# IO_Expansion.net
KiCad netlist of a schematic drawn in Altium Designer
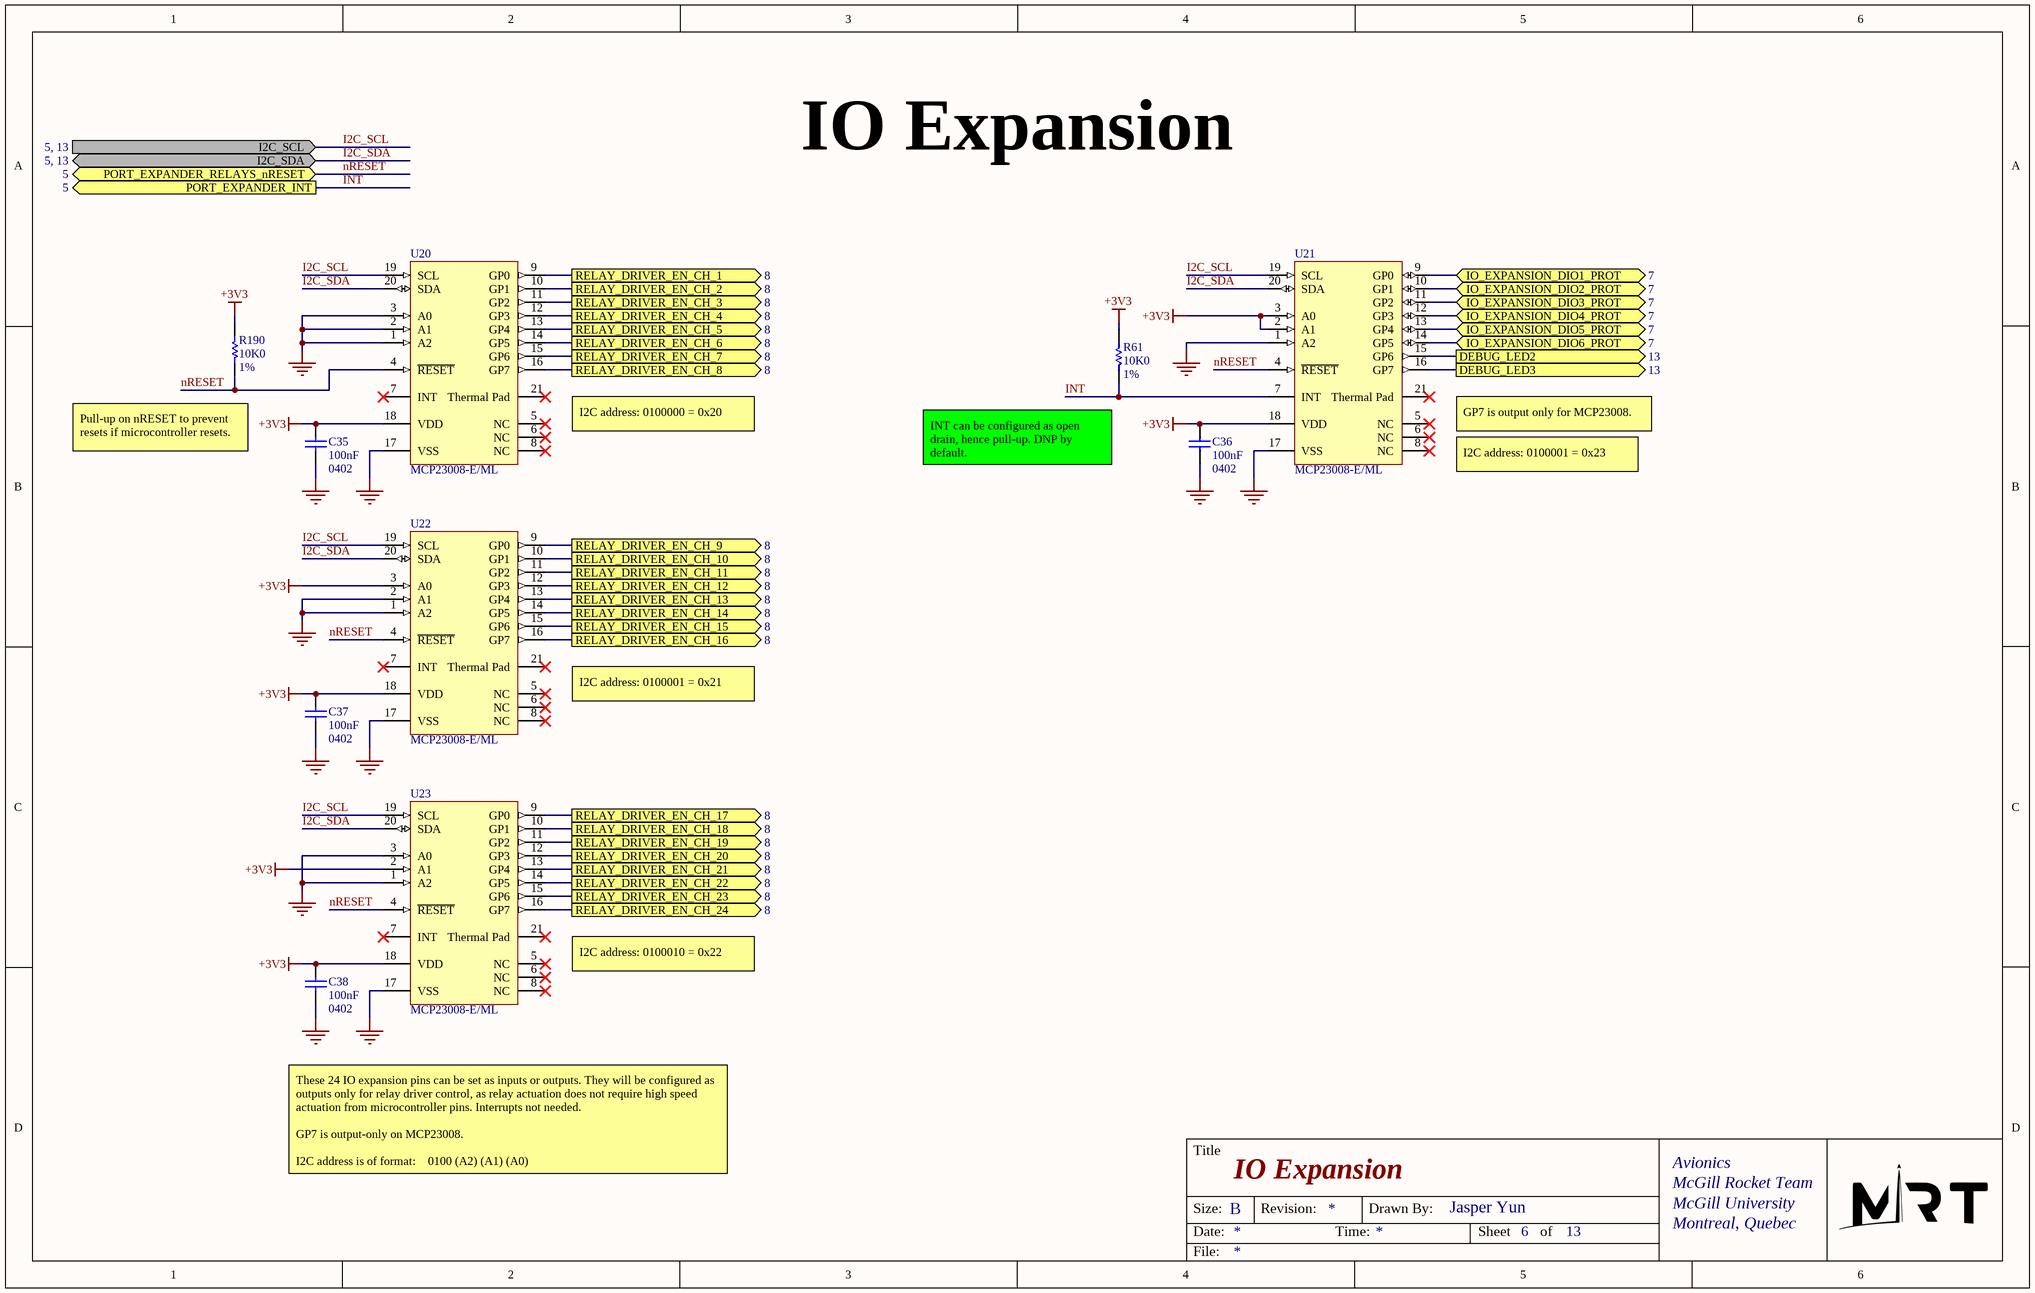
[diagram p0: IO Expansion.SchDoc]

(export (version "E")
  (design (tool "Eeschema 10.0.6"))
  (components
    (comp (ref "C35")
      (value "100nF")
      (footprint "0402 CAP")
      (description "Capacitor")
      (fields (field (name "ALTIUM_VALUE") "0402") (field (name "PUBLISHER") "Altium Limited"))
      (libsource (lib "Miscellaneous Devices") (part "Cap"))
    )
    (comp (ref "C36")
      (value "100nF")
      (footprint "0402 CAP")
      (description "Capacitor")
      (fields (field (name "ALTIUM_VALUE") "0402") (field (name "PUBLISHER") "Altium Limited"))
      (libsource (lib "Miscellaneous Devices") (part "Cap"))
    )
    (comp (ref "C37")
      (value "100nF")
      (footprint "0402 CAP")
      (description "Capacitor")
      (fields (field (name "ALTIUM_VALUE") "0402") (field (name "PUBLISHER") "Altium Limited"))
      (libsource (lib "Miscellaneous Devices") (part "Cap"))
    )
    (comp (ref "C38")
      (value "100nF")
      (footprint "0402 CAP")
      (description "Capacitor")
      (fields (field (name "ALTIUM_VALUE") "0402") (field (name "PUBLISHER") "Altium Limited"))
      (libsource (lib "Miscellaneous Devices") (part "Cap"))
    )
    (comp (ref "R61")
      (value "10K0")
      (footprint "0402 RES")
      (description "Resistor")
      (fields (field (name "ALTIUM_VALUE") "1%") (field (name "PUBLISHER") "Altium Limited"))
      (libsource (lib "Miscellaneous Devices") (part "Res1"))
    )
    (comp (ref "R190")
      (value "10K0")
      (footprint "0402 RES")
      (description "Resistor")
      (fields (field (name "ALTIUM_VALUE") "1%") (field (name "PUBLISHER") "Altium Limited"))
      (libsource (lib "Miscellaneous Devices") (part "Res1"))
    )
    (comp (ref "U20")
      (value "MCP23008-E/ML")
      (footprint "QFN-ML20_M")
      (description "8-Bit I/O Expander with Serial Interface, 20-Pin QFN, Extended Temperature")
      (libsource (lib "Altium Content Vault") (part "PR-BUSIC-MCP23008-21"))
    )
    (comp (ref "U21")
      (value "MCP23008-E/ML")
      (footprint "QFN-ML20_M")
      (description "8-Bit I/O Expander with Serial Interface, 20-Pin QFN, Extended Temperature")
      (libsource (lib "Altium Content Vault") (part "PR-BUSIC-MCP23008-21"))
    )
    (comp (ref "U22")
      (value "MCP23008-E/ML")
      (footprint "QFN-ML20_M")
      (description "8-Bit I/O Expander with Serial Interface, 20-Pin QFN, Extended Temperature")
      (libsource (lib "Altium Content Vault") (part "PR-BUSIC-MCP23008-21"))
    )
    (comp (ref "U23")
      (value "MCP23008-E/ML")
      (footprint "QFN-ML20_M")
      (description "8-Bit I/O Expander with Serial Interface, 20-Pin QFN, Extended Temperature")
      (libsource (lib "Altium Content Vault") (part "PR-BUSIC-MCP23008-21"))
    )
  )
  (nets
    (net (code "1") (name "+3V3") (class "Default")
      (node (ref "C35") (pin "2") (pinfunction "2_2") (pintype "passive"))
      (node (ref "C36") (pin "2") (pinfunction "2_2") (pintype "passive"))
      (node (ref "C37") (pin "2") (pinfunction "2_2") (pintype "passive"))
      (node (ref "C38") (pin "2") (pinfunction "2_2") (pintype "passive"))
      (node (ref "R190") (pin "1") (pinfunction "1_1") (pintype "passive"))
      (node (ref "R61") (pin "1") (pinfunction "1_1") (pintype "passive"))
      (node (ref "U20") (pin "18") (pinfunction "VDD_18") (pintype "power_in"))
      (node (ref "U21") (pin "18") (pinfunction "VDD_18") (pintype "power_in"))
      (node (ref "U21") (pin "2") (pinfunction "A1_2") (pintype "input"))
      (node (ref "U21") (pin "3") (pinfunction "A0_3") (pintype "input"))
      (node (ref "U22") (pin "18") (pinfunction "VDD_18") (pintype "power_in"))
      (node (ref "U22") (pin "3") (pinfunction "A0_3") (pintype "input"))
      (node (ref "U23") (pin "18") (pinfunction "VDD_18") (pintype "power_in"))
      (node (ref "U23") (pin "2") (pinfunction "A1_2") (pintype "input"))
    )
    (net (code "2") (name "/DEBUG_LED2") (class "Default")
      (node (ref "U21") (pin "15") (pinfunction "GP6_15") (pintype "output"))
    )
    (net (code "3") (name "/DEBUG_LED3") (class "Default")
      (node (ref "U21") (pin "16") (pinfunction "GP7_16") (pintype "output"))
    )
    (net (code "4") (name "/I2C_SCL") (class "Default")
      (node (ref "U20") (pin "19") (pinfunction "SCL_19") (pintype "input"))
      (node (ref "U21") (pin "19") (pinfunction "SCL_19") (pintype "input"))
      (node (ref "U22") (pin "19") (pinfunction "SCL_19") (pintype "input"))
      (node (ref "U23") (pin "19") (pinfunction "SCL_19") (pintype "input"))
    )
    (net (code "5") (name "/I2C_SDA") (class "Default")
      (node (ref "U20") (pin "20") (pinfunction "SDA_20") (pintype "bidirectional"))
      (node (ref "U21") (pin "20") (pinfunction "SDA_20") (pintype "bidirectional"))
      (node (ref "U22") (pin "20") (pinfunction "SDA_20") (pintype "bidirectional"))
      (node (ref "U23") (pin "20") (pinfunction "SDA_20") (pintype "bidirectional"))
    )
    (net (code "6") (name "/INT") (class "Default")
      (node (ref "R61") (pin "2") (pinfunction "2_2") (pintype "passive"))
      (node (ref "U21") (pin "7") (pinfunction "INT_7") (pintype "open_collector"))
    )
    (net (code "7") (name "/IO_EXPANSION_DIO1_PROT") (class "Default")
      (node (ref "U21") (pin "9") (pinfunction "GP0_9") (pintype "output"))
    )
    (net (code "8") (name "/IO_EXPANSION_DIO2_PROT") (class "Default")
      (node (ref "U21") (pin "10") (pinfunction "GP1_10") (pintype "output"))
    )
    (net (code "9") (name "/IO_EXPANSION_DIO3_PROT") (class "Default")
      (node (ref "U21") (pin "11") (pinfunction "GP2_11") (pintype "output"))
    )
    (net (code "10") (name "/IO_EXPANSION_DIO4_PROT") (class "Default")
      (node (ref "U21") (pin "12") (pinfunction "GP3_12") (pintype "output"))
    )
    (net (code "11") (name "/IO_EXPANSION_DIO5_PROT") (class "Default")
      (node (ref "U21") (pin "13") (pinfunction "GP4_13") (pintype "output"))
    )
    (net (code "12") (name "/IO_EXPANSION_DIO6_PROT") (class "Default")
      (node (ref "U21") (pin "14") (pinfunction "GP5_14") (pintype "output"))
    )
    (net (code "13") (name "/RELAY_DRIVER_EN_CH_1") (class "Default")
      (node (ref "U20") (pin "9") (pinfunction "GP0_9") (pintype "output"))
    )
    (net (code "14") (name "/RELAY_DRIVER_EN_CH_2") (class "Default")
      (node (ref "U20") (pin "10") (pinfunction "GP1_10") (pintype "output"))
    )
    (net (code "15") (name "/RELAY_DRIVER_EN_CH_3") (class "Default")
      (node (ref "U20") (pin "11") (pinfunction "GP2_11") (pintype "output"))
    )
    (net (code "16") (name "/RELAY_DRIVER_EN_CH_4") (class "Default")
      (node (ref "U20") (pin "12") (pinfunction "GP3_12") (pintype "output"))
    )
    (net (code "17") (name "/RELAY_DRIVER_EN_CH_5") (class "Default")
      (node (ref "U20") (pin "13") (pinfunction "GP4_13") (pintype "output"))
    )
    (net (code "18") (name "/RELAY_DRIVER_EN_CH_6") (class "Default")
      (node (ref "U20") (pin "14") (pinfunction "GP5_14") (pintype "output"))
    )
    (net (code "19") (name "/RELAY_DRIVER_EN_CH_7") (class "Default")
      (node (ref "U20") (pin "15") (pinfunction "GP6_15") (pintype "output"))
    )
    (net (code "20") (name "/RELAY_DRIVER_EN_CH_8") (class "Default")
      (node (ref "U20") (pin "16") (pinfunction "GP7_16") (pintype "output"))
    )
    (net (code "21") (name "/RELAY_DRIVER_EN_CH_9") (class "Default")
      (node (ref "U22") (pin "9") (pinfunction "GP0_9") (pintype "output"))
    )
    (net (code "22") (name "/RELAY_DRIVER_EN_CH_10") (class "Default")
      (node (ref "U22") (pin "10") (pinfunction "GP1_10") (pintype "output"))
    )
    (net (code "23") (name "/RELAY_DRIVER_EN_CH_11") (class "Default")
      (node (ref "U22") (pin "11") (pinfunction "GP2_11") (pintype "output"))
    )
    (net (code "24") (name "/RELAY_DRIVER_EN_CH_12") (class "Default")
      (node (ref "U22") (pin "12") (pinfunction "GP3_12") (pintype "output"))
    )
    (net (code "25") (name "/RELAY_DRIVER_EN_CH_13") (class "Default")
      (node (ref "U22") (pin "13") (pinfunction "GP4_13") (pintype "output"))
    )
    (net (code "26") (name "/RELAY_DRIVER_EN_CH_14") (class "Default")
      (node (ref "U22") (pin "14") (pinfunction "GP5_14") (pintype "output"))
    )
    (net (code "27") (name "/RELAY_DRIVER_EN_CH_15") (class "Default")
      (node (ref "U22") (pin "15") (pinfunction "GP6_15") (pintype "output"))
    )
    (net (code "28") (name "/RELAY_DRIVER_EN_CH_16") (class "Default")
      (node (ref "U22") (pin "16") (pinfunction "GP7_16") (pintype "output"))
    )
    (net (code "29") (name "/RELAY_DRIVER_EN_CH_17") (class "Default")
      (node (ref "U23") (pin "9") (pinfunction "GP0_9") (pintype "output"))
    )
    (net (code "30") (name "/RELAY_DRIVER_EN_CH_18") (class "Default")
      (node (ref "U23") (pin "10") (pinfunction "GP1_10") (pintype "output"))
    )
    (net (code "31") (name "/RELAY_DRIVER_EN_CH_19") (class "Default")
      (node (ref "U23") (pin "11") (pinfunction "GP2_11") (pintype "output"))
    )
    (net (code "32") (name "/RELAY_DRIVER_EN_CH_20") (class "Default")
      (node (ref "U23") (pin "12") (pinfunction "GP3_12") (pintype "output"))
    )
    (net (code "33") (name "/RELAY_DRIVER_EN_CH_21") (class "Default")
      (node (ref "U23") (pin "13") (pinfunction "GP4_13") (pintype "output"))
    )
    (net (code "34") (name "/RELAY_DRIVER_EN_CH_22") (class "Default")
      (node (ref "U23") (pin "14") (pinfunction "GP5_14") (pintype "output"))
    )
    (net (code "35") (name "/RELAY_DRIVER_EN_CH_23") (class "Default")
      (node (ref "U23") (pin "15") (pinfunction "GP6_15") (pintype "output"))
    )
    (net (code "36") (name "/RELAY_DRIVER_EN_CH_24") (class "Default")
      (node (ref "U23") (pin "16") (pinfunction "GP7_16") (pintype "output"))
    )
    (net (code "37") (name "/nRESET") (class "Default")
      (node (ref "R190") (pin "2") (pinfunction "2_2") (pintype "passive"))
      (node (ref "U20") (pin "4") (pinfunction "~{RESET}_4") (pintype "input"))
      (node (ref "U21") (pin "4") (pinfunction "~{RESET}_4") (pintype "input"))
      (node (ref "U22") (pin "4") (pinfunction "~{RESET}_4") (pintype "input"))
      (node (ref "U23") (pin "4") (pinfunction "~{RESET}_4") (pintype "input"))
    )
    (net (code "38") (name "GND") (class "Default")
      (node (ref "C35") (pin "1") (pinfunction "1_1") (pintype "passive"))
      (node (ref "C36") (pin "1") (pinfunction "1_1") (pintype "passive"))
      (node (ref "C37") (pin "1") (pinfunction "1_1") (pintype "passive"))
      (node (ref "C38") (pin "1") (pinfunction "1_1") (pintype "passive"))
      (node (ref "U20") (pin "1") (pinfunction "A2_1") (pintype "input"))
      (node (ref "U20") (pin "17") (pinfunction "VSS_17") (pintype "power_in"))
      (node (ref "U20") (pin "2") (pinfunction "A1_2") (pintype "input"))
      (node (ref "U20") (pin "3") (pinfunction "A0_3") (pintype "input"))
      (node (ref "U21") (pin "1") (pinfunction "A2_1") (pintype "input"))
      (node (ref "U21") (pin "17") (pinfunction "VSS_17") (pintype "power_in"))
      (node (ref "U22") (pin "1") (pinfunction "A2_1") (pintype "input"))
      (node (ref "U22") (pin "17") (pinfunction "VSS_17") (pintype "power_in"))
      (node (ref "U22") (pin "2") (pinfunction "A1_2") (pintype "input"))
      (node (ref "U23") (pin "1") (pinfunction "A2_1") (pintype "input"))
      (node (ref "U23") (pin "17") (pinfunction "VSS_17") (pintype "power_in"))
      (node (ref "U23") (pin "3") (pinfunction "A0_3") (pintype "input"))
    )
    (net (code "39") (name "unconnected-(U20-INT-Pad7)") (class "Default")
      (node (ref "U20") (pin "7") (pinfunction "INT_7") (pintype "open_collector+no_connect"))
    )
    (net (code "40") (name "unconnected-(U20-NC-Pad5)") (class "Default")
      (node (ref "U20") (pin "5") (pinfunction "NC_5") (pintype "passive+no_connect"))
    )
    (net (code "41") (name "unconnected-(U20-NC-Pad6)") (class "Default")
      (node (ref "U20") (pin "6") (pinfunction "NC_6") (pintype "passive+no_connect"))
    )
    (net (code "42") (name "unconnected-(U20-NC-Pad8)") (class "Default")
      (node (ref "U20") (pin "8") (pinfunction "NC_8") (pintype "passive+no_connect"))
    )
    (net (code "43") (name "unconnected-(U20-Thermal_Pad-Pad21)") (class "Default")
      (node (ref "U20") (pin "21") (pinfunction "Thermal_Pad_21") (pintype "passive+no_connect"))
    )
    (net (code "44") (name "unconnected-(U21-NC-Pad5)") (class "Default")
      (node (ref "U21") (pin "5") (pinfunction "NC_5") (pintype "passive+no_connect"))
    )
    (net (code "45") (name "unconnected-(U21-NC-Pad6)") (class "Default")
      (node (ref "U21") (pin "6") (pinfunction "NC_6") (pintype "passive+no_connect"))
    )
    (net (code "46") (name "unconnected-(U21-NC-Pad8)") (class "Default")
      (node (ref "U21") (pin "8") (pinfunction "NC_8") (pintype "passive+no_connect"))
    )
    (net (code "47") (name "unconnected-(U21-Thermal_Pad-Pad21)") (class "Default")
      (node (ref "U21") (pin "21") (pinfunction "Thermal_Pad_21") (pintype "passive+no_connect"))
    )
    (net (code "48") (name "unconnected-(U22-INT-Pad7)") (class "Default")
      (node (ref "U22") (pin "7") (pinfunction "INT_7") (pintype "open_collector+no_connect"))
    )
    (net (code "49") (name "unconnected-(U22-NC-Pad5)") (class "Default")
      (node (ref "U22") (pin "5") (pinfunction "NC_5") (pintype "passive+no_connect"))
    )
    (net (code "50") (name "unconnected-(U22-NC-Pad6)") (class "Default")
      (node (ref "U22") (pin "6") (pinfunction "NC_6") (pintype "passive+no_connect"))
    )
    (net (code "51") (name "unconnected-(U22-NC-Pad8)") (class "Default")
      (node (ref "U22") (pin "8") (pinfunction "NC_8") (pintype "passive+no_connect"))
    )
    (net (code "52") (name "unconnected-(U22-Thermal_Pad-Pad21)") (class "Default")
      (node (ref "U22") (pin "21") (pinfunction "Thermal_Pad_21") (pintype "passive+no_connect"))
    )
    (net (code "53") (name "unconnected-(U23-INT-Pad7)") (class "Default")
      (node (ref "U23") (pin "7") (pinfunction "INT_7") (pintype "open_collector+no_connect"))
    )
    (net (code "54") (name "unconnected-(U23-NC-Pad5)") (class "Default")
      (node (ref "U23") (pin "5") (pinfunction "NC_5") (pintype "passive+no_connect"))
    )
    (net (code "55") (name "unconnected-(U23-NC-Pad6)") (class "Default")
      (node (ref "U23") (pin "6") (pinfunction "NC_6") (pintype "passive+no_connect"))
    )
    (net (code "56") (name "unconnected-(U23-NC-Pad8)") (class "Default")
      (node (ref "U23") (pin "8") (pinfunction "NC_8") (pintype "passive+no_connect"))
    )
    (net (code "57") (name "unconnected-(U23-Thermal_Pad-Pad21)") (class "Default")
      (node (ref "U23") (pin "21") (pinfunction "Thermal_Pad_21") (pintype "passive+no_connect"))
    )
  )
)
